# CAN_QSPI.net
KiCad netlist of a schematic drawn in Altium Designer
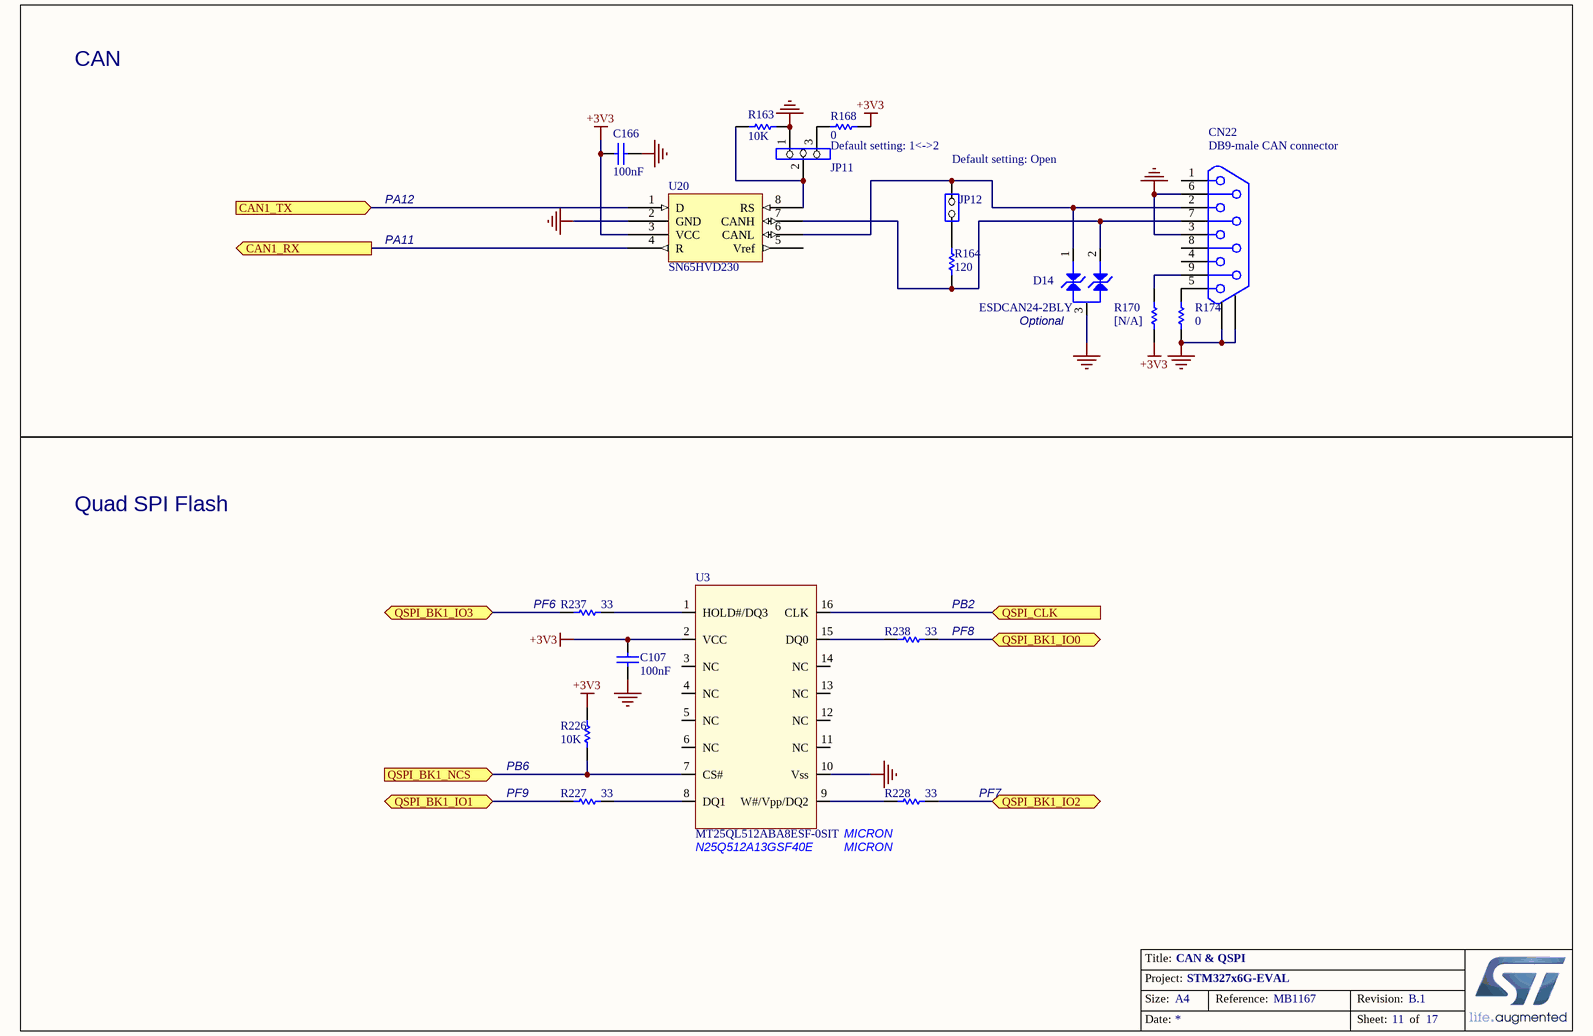
[diagram p0: CAN&QSPI.SchDoc]

(export (version "E")
  (design (tool "Eeschema 10.0.6"))
  (components
    (comp (ref "C107")
      (value "100nF")
      (footprint "0402C")
      (description "Capacitor")
      (fields (field (name "PUBLISHER") "Altium Limited"))
      (libsource (lib "Miscellaneous Devices") (part "Cap"))
    )
    (comp (ref "C166")
      (value "100nF")
      (footprint "0603C")
      (description "Capacitor")
      (fields (field (name "PUBLISHER") "Altium Limited"))
      (libsource (lib "Miscellaneous Devices") (part "Cap"))
    )
    (comp (ref "CN22")
      (value "DB9-male CAN connector")
      (footprint "DB9/M")
      (libsource (lib "mb1045") (part "DB9-CAN"))
    )
    (comp (ref "D14")
      (value "ESDCAN24-2BLY")
      (footprint "SOT-23")
      (libsource (lib "mb1045") (part "ESDCAN24-2BLY"))
    )
    (comp (ref "JP11") (value "~") (footprint "SIP3") (libsource (lib "STR910_SCHLIB") (part "Jumper3")))
    (comp (ref "JP12") (value "~") (footprint "SIP2") (libsource (lib "*") (part "JP2")))
    (comp (ref "R163")
      (value "10K")
      (footprint "0603R")
      (description "Resistor")
      (fields (field (name "PUBLISHER") "Altium Limited"))
      (libsource (lib "Miscellaneous Devices") (part "Res1"))
    )
    (comp (ref "R164")
      (value "120")
      (footprint "0603R")
      (description "Resistor")
      (fields (field (name "PUBLISHER") "Altium Limited"))
      (libsource (lib "Miscellaneous Devices") (part "res1"))
    )
    (comp (ref "R168")
      (value "0")
      (footprint "0603R")
      (description "Resistor")
      (fields (field (name "PUBLISHER") "Altium Limited"))
      (libsource (lib "Miscellaneous Devices") (part "res1"))
    )
    (comp (ref "R170")
      (value "[N/A]")
      (footprint "0603R")
      (description "Resistor")
      (fields (field (name "PUBLISHER") "Altium Limited"))
      (libsource (lib "Miscellaneous Devices") (part "res1"))
    )
    (comp (ref "R174")
      (value "0")
      (footprint "0603R")
      (description "Resistor")
      (fields (field (name "PUBLISHER") "Altium Limited"))
      (libsource (lib "Miscellaneous Devices") (part "res1"))
    )
    (comp (ref "R226")
      (value "10K")
      (footprint "0402R")
      (description "Resistor")
      (fields (field (name "PUBLISHER") "Altium Limited"))
      (libsource (lib "Miscellaneous Devices") (part "res1"))
    )
    (comp (ref "R227")
      (value "33")
      (footprint "0603R")
      (description "Resistor")
      (fields (field (name "PUBLISHER") "Altium Limited"))
      (libsource (lib "Miscellaneous Devices") (part "Res1"))
    )
    (comp (ref "R228")
      (value "33")
      (footprint "0603R")
      (description "Resistor")
      (fields (field (name "PUBLISHER") "Altium Limited"))
      (libsource (lib "Miscellaneous Devices") (part "Res1"))
    )
    (comp (ref "R237")
      (value "33")
      (footprint "0603R")
      (description "Resistor")
      (fields (field (name "PUBLISHER") "Altium Limited"))
      (libsource (lib "Miscellaneous Devices") (part "Res1"))
    )
    (comp (ref "R238")
      (value "33")
      (footprint "0603R")
      (description "Resistor")
      (fields (field (name "PUBLISHER") "Altium Limited"))
      (libsource (lib "Miscellaneous Devices") (part "Res1"))
    )
    (comp (ref "U3")
      (value "MT25QL512ABA8ESF-0SIT")
      (footprint "SOIC16W_1R27_10R3X10R33")
      (libsource (lib "MB1167") (part "QSPI_16pins"))
    )
    (comp (ref "U20")
      (value "SN65HVD230")
      (footprint "SOIC8_1R27_4R9X6")
      (libsource (lib "STR910_SCHLIB") (part "SN65HVD230D"))
    )
  )
  (nets
    (net (code "1") (name "+3V3") (class "Default")
      (node (ref "C107") (pin "1") (pinfunction "1_1") (pintype "passive"))
      (node (ref "C166") (pin "1") (pinfunction "1_1") (pintype "passive"))
      (node (ref "R168") (pin "2") (pinfunction "2_2") (pintype "passive"))
      (node (ref "R170") (pin "1") (pinfunction "1_1") (pintype "passive"))
      (node (ref "R226") (pin "1") (pinfunction "1_1") (pintype "passive"))
      (node (ref "U20") (pin "3") (pinfunction "VCC_3") (pintype "power_in"))
      (node (ref "U3") (pin "2") (pinfunction "VCC_2") (pintype "passive"))
    )
    (net (code "2") (name "/CAN1_RX") (class "Default")
      (node (ref "U20") (pin "4") (pinfunction "R_4") (pintype "output"))
    )
    (net (code "3") (name "/CAN1_TX") (class "Default")
      (node (ref "U20") (pin "1") (pinfunction "D_1") (pintype "input"))
    )
    (net (code "4") (name "/QSPI_BK1_IO0") (class "Default")
      (node (ref "R238") (pin "1") (pinfunction "1_1") (pintype "passive"))
    )
    (net (code "5") (name "/QSPI_BK1_IO1") (class "Default")
      (node (ref "R227") (pin "2") (pinfunction "2_2") (pintype "passive"))
    )
    (net (code "6") (name "/QSPI_BK1_IO2") (class "Default")
      (node (ref "R228") (pin "1") (pinfunction "1_1") (pintype "passive"))
    )
    (net (code "7") (name "/QSPI_BK1_IO3") (class "Default")
      (node (ref "R237") (pin "2") (pinfunction "2_2") (pintype "passive"))
    )
    (net (code "8") (name "/QSPI_BK1_NCS") (class "Default")
      (node (ref "R226") (pin "2") (pinfunction "2_2") (pintype "passive"))
      (node (ref "U3") (pin "7") (pinfunction "CS#_7") (pintype "passive"))
    )
    (net (code "9") (name "/QSPI_CLK") (class "Default")
      (node (ref "U3") (pin "16") (pinfunction "CLK_16") (pintype "passive"))
    )
    (net (code "10") (name "GND") (class "Default")
      (node (ref "C107") (pin "2") (pinfunction "2_2") (pintype "passive"))
      (node (ref "C166") (pin "2") (pinfunction "2_2") (pintype "passive"))
      (node (ref "CN22") (pin "10") (pinfunction "10_10") (pintype "passive"))
      (node (ref "CN22") (pin "11") (pinfunction "11_11") (pintype "passive"))
      (node (ref "CN22") (pin "3") (pinfunction "3_3") (pintype "passive"))
      (node (ref "CN22") (pin "6") (pinfunction "6_6") (pintype "passive"))
      (node (ref "D14") (pin "3") (pinfunction "3_3") (pintype "passive"))
      (node (ref "JP11") (pin "1") (pintype "passive"))
      (node (ref "R163") (pin "2") (pinfunction "2_2") (pintype "passive"))
      (node (ref "R174") (pin "1") (pinfunction "1_1") (pintype "passive"))
      (node (ref "U20") (pin "2") (pinfunction "GND_2") (pintype "power_in"))
      (node (ref "U3") (pin "10") (pinfunction "Vss_10") (pintype "passive"))
    )
    (net (code "11") (name "Net-(CN22-Pad5)") (class "Default")
      (node (ref "CN22") (pin "5") (pinfunction "5_5") (pintype "passive"))
      (node (ref "R174") (pin "2") (pinfunction "2_2") (pintype "passive"))
    )
    (net (code "12") (name "Net-(CN22-Pad9)") (class "Default")
      (node (ref "CN22") (pin "9") (pinfunction "9_9") (pintype "passive"))
      (node (ref "R170") (pin "2") (pinfunction "2_2") (pintype "passive"))
    )
    (net (code "13") (name "Net-(JP11-Pad3)") (class "Default")
      (node (ref "JP11") (pin "3") (pintype "passive"))
      (node (ref "R168") (pin "1") (pinfunction "1_1") (pintype "passive"))
    )
    (net (code "14") (name "Net-(JP12-COMMON)") (class "Default")
      (node (ref "JP12") (pin "1") (pinfunction "COMMON_1") (pintype "passive"))
      (node (ref "R164") (pin "2") (pinfunction "2_2") (pintype "passive"))
    )
    (net (code "15") (name "Net-(JP12-NO)") (class "Default")
      (node (ref "CN22") (pin "2") (pinfunction "2_2") (pintype "passive"))
      (node (ref "D14") (pin "1") (pinfunction "1_1") (pintype "passive"))
      (node (ref "JP12") (pin "2") (pinfunction "NO_2") (pintype "passive"))
      (node (ref "U20") (pin "6") (pinfunction "CANL_6") (pintype "bidirectional"))
    )
    (net (code "16") (name "Net-(U3-DQ0)") (class "Default")
      (node (ref "R238") (pin "2") (pinfunction "2_2") (pintype "passive"))
      (node (ref "U3") (pin "15") (pinfunction "DQ0_15") (pintype "passive"))
    )
    (net (code "17") (name "Net-(U3-DQ1)") (class "Default")
      (node (ref "R227") (pin "1") (pinfunction "1_1") (pintype "passive"))
      (node (ref "U3") (pin "8") (pinfunction "DQ1_8") (pintype "passive"))
    )
    (net (code "18") (name "Net-(U3-HOLD#{slash}DQ3)") (class "Default")
      (node (ref "R237") (pin "1") (pinfunction "1_1") (pintype "passive"))
      (node (ref "U3") (pin "1") (pinfunction "HOLD#/DQ3_1") (pintype "passive"))
    )
    (net (code "19") (name "Net-(U3-W#{slash}Vpp{slash}DQ2)") (class "Default")
      (node (ref "R228") (pin "2") (pinfunction "2_2") (pintype "passive"))
      (node (ref "U3") (pin "9") (pinfunction "W#/Vpp/DQ2_9") (pintype "passive"))
    )
    (net (code "20") (name "Net-(U20-CANH)") (class "Default")
      (node (ref "CN22") (pin "7") (pinfunction "7_7") (pintype "passive"))
      (node (ref "D14") (pin "2") (pinfunction "2_2") (pintype "passive"))
      (node (ref "R164") (pin "1") (pinfunction "1_1") (pintype "passive"))
      (node (ref "U20") (pin "7") (pinfunction "CANH_7") (pintype "bidirectional"))
    )
    (net (code "21") (name "Net-(U20-RS)") (class "Default")
      (node (ref "JP11") (pin "2") (pintype "passive"))
      (node (ref "R163") (pin "1") (pinfunction "1_1") (pintype "passive"))
      (node (ref "U20") (pin "8") (pinfunction "RS_8") (pintype "input"))
    )
    (net (code "22") (name "unconnected-(CN22-Pad1)") (class "Default")
      (node (ref "CN22") (pin "1") (pinfunction "1_1") (pintype "passive"))
    )
    (net (code "23") (name "unconnected-(CN22-Pad4)") (class "Default")
      (node (ref "CN22") (pin "4") (pinfunction "4_4") (pintype "passive"))
    )
    (net (code "24") (name "unconnected-(CN22-Pad8)") (class "Default")
      (node (ref "CN22") (pin "8") (pinfunction "8_8") (pintype "passive"))
    )
    (net (code "25") (name "unconnected-(U3-NC-Pad3)") (class "Default")
      (node (ref "U3") (pin "3") (pinfunction "NC_3") (pintype "passive"))
    )
    (net (code "26") (name "unconnected-(U3-NC-Pad4)") (class "Default")
      (node (ref "U3") (pin "4") (pinfunction "NC_4") (pintype "passive"))
    )
    (net (code "27") (name "unconnected-(U3-NC-Pad5)") (class "Default")
      (node (ref "U3") (pin "5") (pinfunction "NC_5") (pintype "passive"))
    )
    (net (code "28") (name "unconnected-(U3-NC-Pad6)") (class "Default")
      (node (ref "U3") (pin "6") (pinfunction "NC_6") (pintype "passive"))
    )
    (net (code "29") (name "unconnected-(U3-NC-Pad11)") (class "Default")
      (node (ref "U3") (pin "11") (pinfunction "NC_11") (pintype "passive"))
    )
    (net (code "30") (name "unconnected-(U3-NC-Pad12)") (class "Default")
      (node (ref "U3") (pin "12") (pinfunction "NC_12") (pintype "passive"))
    )
    (net (code "31") (name "unconnected-(U3-NC-Pad13)") (class "Default")
      (node (ref "U3") (pin "13") (pinfunction "NC_13") (pintype "passive"))
    )
    (net (code "32") (name "unconnected-(U3-NC-Pad14)") (class "Default")
      (node (ref "U3") (pin "14") (pinfunction "NC_14") (pintype "passive"))
    )
    (net (code "33") (name "unconnected-(U20-Vref-Pad5)") (class "Default")
      (node (ref "U20") (pin "5") (pinfunction "Vref_5") (pintype "output"))
    )
  )
)
